# LOGICA_NAO.net
KiCad netlist of a schematic drawn in EAGLE
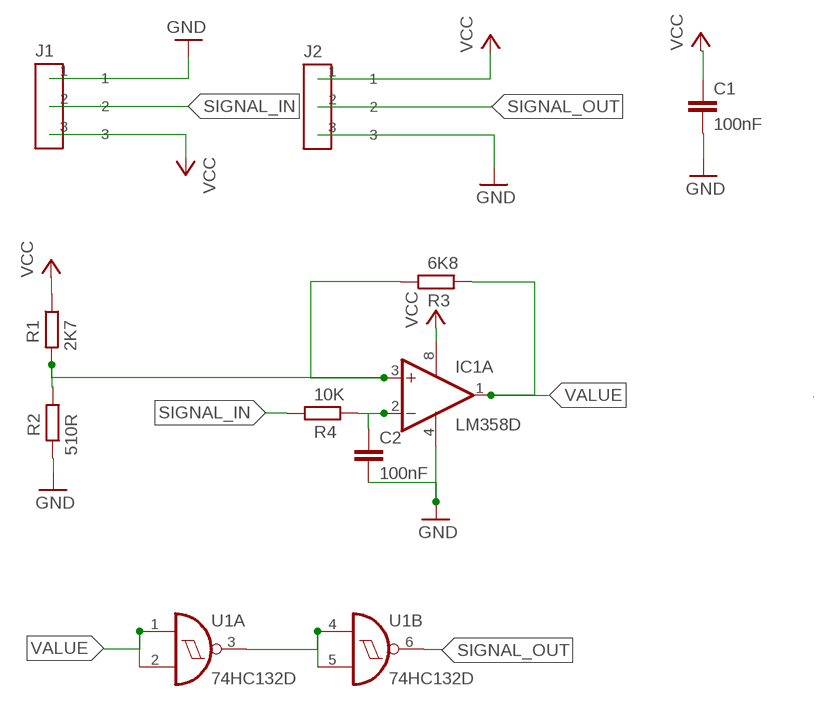
[diagram p0: schematic, sheet 1]

(export (version "E")
  (design (tool "Eeschema 10.0.6"))
  (components
    (comp (ref "C1")
      (value "100nF")
      (footprint "eagle-import:C0805")
      (libsource (lib "eagle-import") (part "C-EUC0805"))
    )
    (comp (ref "C2")
      (value "100nF")
      (footprint "eagle-import:C0805")
      (libsource (lib "eagle-import") (part "C-EUC0805"))
    )
    (comp (ref "IC1")
      (value "LM358D")
      (footprint "eagle-import:SO08")
      (libsource (lib "eagle-import") (part "LM358D"))
    )
    (comp (ref "J1")
      (value "CONECTOR_MACHO")
      (footprint "eagle-import:3CONECTOR")
      (libsource (lib "eagle-import") (part "CONECTOR_MACHO"))
    )
    (comp (ref "J2")
      (value "CONECTOR_FEMEA")
      (footprint "eagle-import:3CONECTOR")
      (libsource (lib "eagle-import") (part "CONECTOR_FEMEA"))
    )
    (comp (ref "R1")
      (value "2K7")
      (footprint "eagle-import:R0805W")
      (libsource (lib "eagle-import") (part "R-EU_R0805W"))
    )
    (comp (ref "R2")
      (value "510R")
      (footprint "eagle-import:R0805W")
      (libsource (lib "eagle-import") (part "R-EU_R0805W"))
    )
    (comp (ref "R3")
      (value "6K8")
      (footprint "eagle-import:R0805W")
      (libsource (lib "eagle-import") (part "R-EU_R0805W"))
    )
    (comp (ref "R4")
      (value "10K")
      (footprint "eagle-import:R0805W")
      (libsource (lib "eagle-import") (part "R-EU_R0805W"))
    )
    (comp (ref "U1")
      (value "74HC132D")
      (footprint "eagle-import:SO14")
      (libsource (lib "eagle-import") (part "74132DHC"))
    )
  )
  (nets
    (net (code "1") (name "GND") (class "Default")
      (node (ref "C1") (pin "2") (pinfunction "2_2") (pintype "passive"))
      (node (ref "C2") (pin "2") (pinfunction "2_2") (pintype "passive"))
      (node (ref "IC1") (pin "4") (pinfunction "V-_4") (pintype "power_in"))
      (node (ref "J1") (pin "1") (pinfunction "1_1") (pintype "bidirectional"))
      (node (ref "J2") (pin "3") (pinfunction "3_3") (pintype "bidirectional"))
      (node (ref "R2") (pin "2") (pinfunction "2_2") (pintype "passive"))
    )
    (net (code "2") (name "Net-(IC1A-+IN)") (class "Default")
      (node (ref "IC1") (pin "3") (pinfunction "+IN_3") (pintype "input"))
      (node (ref "R1") (pin "2") (pinfunction "2_2") (pintype "passive"))
      (node (ref "R2") (pin "1") (pinfunction "1_1") (pintype "passive"))
      (node (ref "R3") (pin "1") (pinfunction "1_1") (pintype "passive"))
    )
    (net (code "3") (name "Net-(IC1A--IN)") (class "Default")
      (node (ref "C2") (pin "1") (pinfunction "1_1") (pintype "passive"))
      (node (ref "IC1") (pin "2") (pinfunction "-IN_2") (pintype "input"))
      (node (ref "R4") (pin "2") (pinfunction "2_2") (pintype "passive"))
    )
    (net (code "4") (name "Net-(U1A-O)") (class "Default")
      (node (ref "U1") (pin "3") (pinfunction "O_3") (pintype "output"))
      (node (ref "U1") (pin "4") (pinfunction "I0_4") (pintype "input"))
      (node (ref "U1") (pin "5") (pinfunction "I1_5") (pintype "input"))
    )
    (net (code "5") (name "SIGNAL_IN") (class "Default")
      (node (ref "J1") (pin "2") (pinfunction "2_2") (pintype "bidirectional"))
      (node (ref "R4") (pin "1") (pinfunction "1_1") (pintype "passive"))
    )
    (net (code "6") (name "SIGNAL_OUT") (class "Default")
      (node (ref "J2") (pin "2") (pinfunction "2_2") (pintype "bidirectional"))
      (node (ref "U1") (pin "6") (pinfunction "O_6") (pintype "output"))
    )
    (net (code "7") (name "VALUE") (class "Default")
      (node (ref "IC1") (pin "1") (pinfunction "OUT_1") (pintype "output"))
      (node (ref "R3") (pin "2") (pinfunction "2_2") (pintype "passive"))
      (node (ref "U1") (pin "1") (pinfunction "I0_1") (pintype "input"))
      (node (ref "U1") (pin "2") (pinfunction "I1_2") (pintype "input"))
    )
    (net (code "8") (name "VCC") (class "Default")
      (node (ref "C1") (pin "1") (pinfunction "1_1") (pintype "passive"))
      (node (ref "IC1") (pin "8") (pinfunction "V+_8") (pintype "power_in"))
      (node (ref "J1") (pin "3") (pinfunction "3_3") (pintype "bidirectional"))
      (node (ref "J2") (pin "1") (pinfunction "1_1") (pintype "bidirectional"))
      (node (ref "R1") (pin "1") (pinfunction "1_1") (pintype "passive"))
    )
  )
)
